# emission.net
KiCad netlist of a schematic drawn in EAGLE
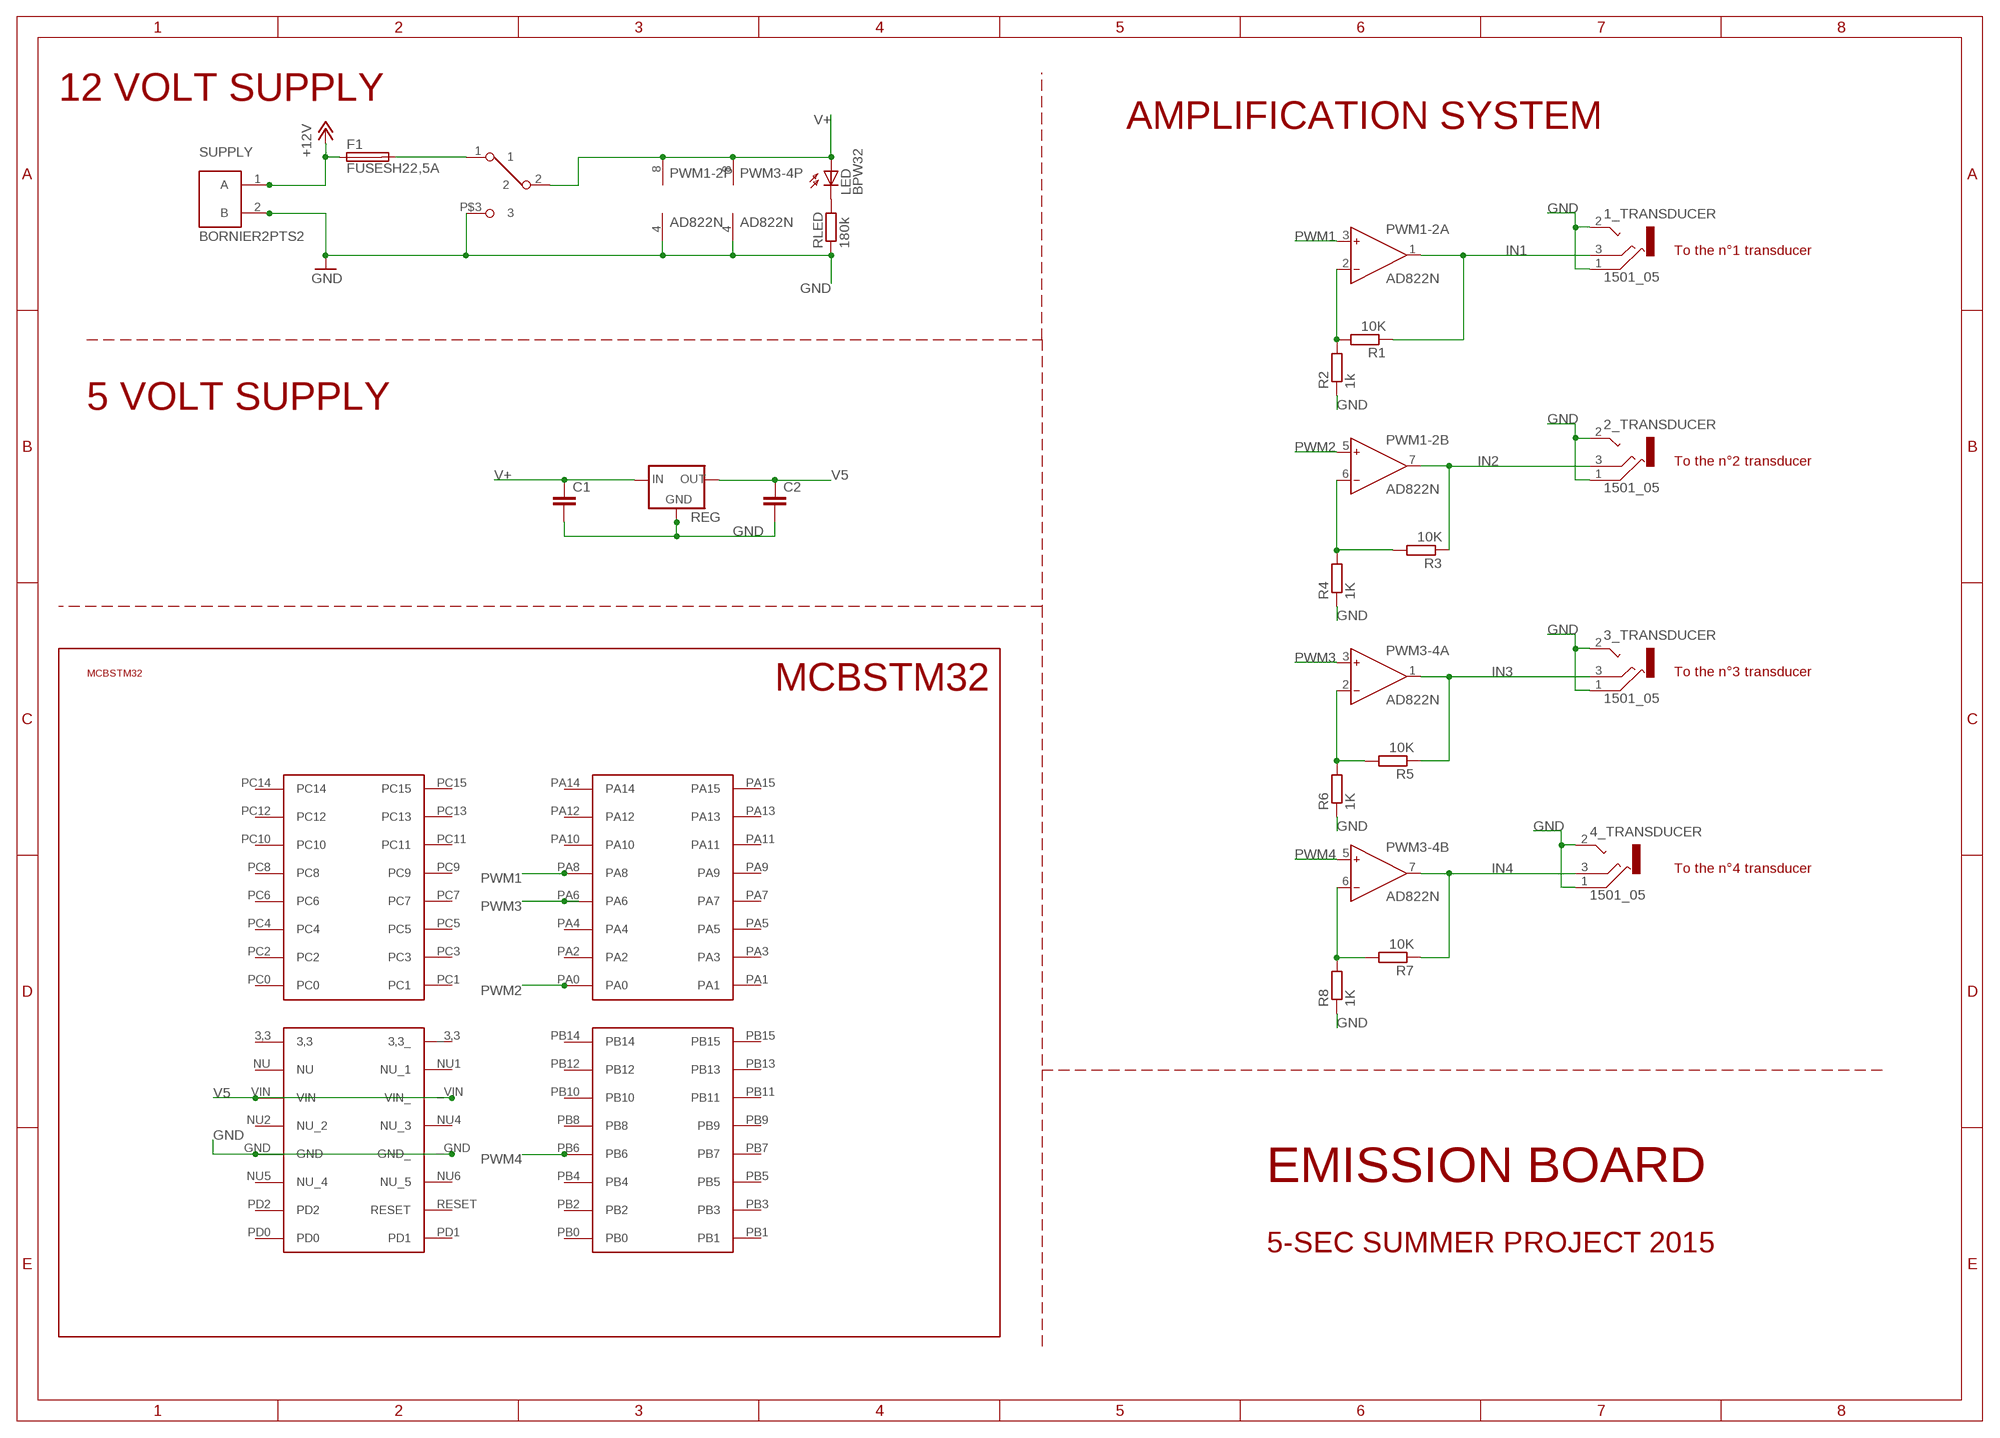
[diagram p0: schematic, sheet 1]

(export (version "E")
  (design (tool "Eeschema 10.0.6"))
  (components
    (comp (ref "1_TRANSDUCER")
      (value "1501_05")
      (footprint "eagle-import:1501_05")
      (libsource (lib "eagle-import") (part "1501_05"))
    )
    (comp (ref "2_TRANSDUCER")
      (value "1501_05")
      (footprint "eagle-import:1501_05")
      (libsource (lib "eagle-import") (part "1501_05"))
    )
    (comp (ref "3_TRANSDUCER")
      (value "1501_05")
      (footprint "eagle-import:1501_05")
      (libsource (lib "eagle-import") (part "1501_05"))
    )
    (comp (ref "4_TRANSDUCER")
      (value "1501_05")
      (footprint "eagle-import:1501_05")
      (libsource (lib "eagle-import") (part "1501_05"))
    )
    (comp (ref "C1")
      (value "C-EU050-030X075")
      (footprint "eagle-import:C050-030X075")
      (libsource (lib "eagle-import") (part "C-EU050-030X075"))
    )
    (comp (ref "C2")
      (value "C-EU050-030X075")
      (footprint "eagle-import:C050-030X075")
      (libsource (lib "eagle-import") (part "C-EU050-030X075"))
    )
    (comp (ref "F1")
      (value "FUSESH22,5A")
      (footprint "eagle-import:SH22,5A")
      (libsource (lib "eagle-import") (part "FUSESH22,5A"))
    )
    (comp (ref "LED")
      (value "BPW32")
      (footprint "eagle-import:BPW32")
      (libsource (lib "eagle-import") (part "BPW32"))
    )
    (comp (ref "MCBSTM1")
      (value "CONNECTOR_MCBSTM32")
      (footprint "eagle-import:CONNECTORSTM")
      (libsource (lib "eagle-import") (part "CONNECTOR_MCBSTM32"))
    )
    (comp (ref "PWM1-2")
      (value "AD822N")
      (footprint "eagle-import:DIL08")
      (libsource (lib "eagle-import") (part "AD822N"))
    )
    (comp (ref "PWM3-4")
      (value "AD822N")
      (footprint "eagle-import:DIL08")
      (libsource (lib "eagle-import") (part "AD822N"))
    )
    (comp (ref "R1")
      (value "10K")
      (footprint "eagle-import:P0613_15")
      (libsource (lib "eagle-import") (part "R-EU_0613/15"))
    )
    (comp (ref "R2")
      (value "1k")
      (footprint "eagle-import:P0613_15")
      (libsource (lib "eagle-import") (part "R-EU_0613/15"))
    )
    (comp (ref "R3")
      (value "10K")
      (footprint "eagle-import:P0613_15")
      (libsource (lib "eagle-import") (part "R-EU_0613/15"))
    )
    (comp (ref "R4")
      (value "1K")
      (footprint "eagle-import:P0613_15")
      (libsource (lib "eagle-import") (part "R-EU_0613/15"))
    )
    (comp (ref "R5")
      (value "10K")
      (footprint "eagle-import:P0613_15")
      (libsource (lib "eagle-import") (part "R-EU_0613/15"))
    )
    (comp (ref "R6")
      (value "1K")
      (footprint "eagle-import:P0613_15")
      (libsource (lib "eagle-import") (part "R-EU_0613/15"))
    )
    (comp (ref "R7")
      (value "10K")
      (footprint "eagle-import:P0613_15")
      (libsource (lib "eagle-import") (part "R-EU_0613/15"))
    )
    (comp (ref "R8")
      (value "1K")
      (footprint "eagle-import:P0613_15")
      (libsource (lib "eagle-import") (part "R-EU_0613/15"))
    )
    (comp (ref "REG")
      (value "78XXS")
      (footprint "eagle-import:78XXS")
      (libsource (lib "eagle-import") (part "78XXS"))
    )
    (comp (ref "RLED")
      (value "180k")
      (footprint "eagle-import:P0613_15")
      (libsource (lib "eagle-import") (part "resistor_R-EU_0613/15"))
    )
    (comp (ref "SUPPLY")
      (value "BORNIER2PTS2")
      (footprint "eagle-import:BORN2X5.08")
      (libsource (lib "eagle-import") (part "BORNIER2PTS2"))
    )
    (comp (ref "U$2")
      (value "SWITCH_CKCOMPONENT")
      (footprint "eagle-import:SWITCH_CKCOMPONENT")
      (libsource (lib "eagle-import") (part "SWITCH_CKCOMPONENT"))
    )
  )
  (nets
    (net (code "1") (name "+12V") (class "Default")
      (node (ref "F1") (pin "1") (pinfunction "1_1") (pintype "passive"))
      (node (ref "SUPPLY") (pin "1") (pinfunction "A_1") (pintype "bidirectional"))
    )
    (net (code "2") (name "/IN1") (class "Default")
      (node (ref "1_TRANSDUCER") (pin "3") (pinfunction "3_3") (pintype "passive"))
      (node (ref "PWM1-2") (pin "1") (pinfunction "OUT_1") (pintype "output"))
      (node (ref "R1") (pin "1") (pinfunction "1_1") (pintype "passive"))
    )
    (net (code "3") (name "/IN2") (class "Default")
      (node (ref "2_TRANSDUCER") (pin "3") (pinfunction "3_3") (pintype "passive"))
      (node (ref "PWM1-2") (pin "7") (pinfunction "OUT_7") (pintype "output"))
      (node (ref "R3") (pin "1") (pinfunction "1_1") (pintype "passive"))
    )
    (net (code "4") (name "/IN3") (class "Default")
      (node (ref "3_TRANSDUCER") (pin "3") (pinfunction "3_3") (pintype "passive"))
      (node (ref "PWM3-4") (pin "1") (pinfunction "OUT_1") (pintype "output"))
      (node (ref "R5") (pin "1") (pinfunction "1_1") (pintype "passive"))
    )
    (net (code "5") (name "/IN4") (class "Default")
      (node (ref "4_TRANSDUCER") (pin "3") (pinfunction "3_3") (pintype "passive"))
      (node (ref "PWM3-4") (pin "7") (pinfunction "OUT_7") (pintype "output"))
      (node (ref "R7") (pin "1") (pinfunction "1_1") (pintype "passive"))
    )
    (net (code "6") (name "/PWM1") (class "Default")
      (node (ref "MCBSTM1") (pin "PA8") (pinfunction "PA8_PA8") (pintype "bidirectional"))
      (node (ref "PWM1-2") (pin "3") (pinfunction "IN+_3") (pintype "input"))
    )
    (net (code "7") (name "/PWM2") (class "Default")
      (node (ref "MCBSTM1") (pin "PA0") (pinfunction "PA0_PA0") (pintype "bidirectional"))
      (node (ref "PWM1-2") (pin "5") (pinfunction "IN+_5") (pintype "input"))
    )
    (net (code "8") (name "/PWM3") (class "Default")
      (node (ref "MCBSTM1") (pin "PA6") (pinfunction "PA6_PA6") (pintype "bidirectional"))
      (node (ref "PWM3-4") (pin "3") (pinfunction "IN+_3") (pintype "input"))
    )
    (net (code "9") (name "/PWM4") (class "Default")
      (node (ref "MCBSTM1") (pin "PB6") (pinfunction "PB6_PB6") (pintype "bidirectional"))
      (node (ref "PWM3-4") (pin "5") (pinfunction "IN+_5") (pintype "input"))
    )
    (net (code "10") (name "/V+") (class "Default")
      (node (ref "C1") (pin "1") (pinfunction "1_1") (pintype "passive"))
      (node (ref "LED") (pin "A") (pinfunction "A_A") (pintype "passive"))
      (node (ref "PWM1-2") (pin "8") (pinfunction "V+_8") (pintype "power_in"))
      (node (ref "PWM3-4") (pin "8") (pinfunction "V+_8") (pintype "power_in"))
      (node (ref "REG") (pin "IN") (pinfunction "IN_IN") (pintype "input"))
      (node (ref "U$2") (pin "2") (pinfunction "2_2") (pintype "bidirectional"))
    )
    (net (code "11") (name "/V5") (class "Default")
      (node (ref "C2") (pin "1") (pinfunction "1_1") (pintype "passive"))
      (node (ref "MCBSTM1") (pin "VIN") (pinfunction "VIN_VIN") (pintype "bidirectional"))
      (node (ref "MCBSTM1") (pin "_VIN") (pinfunction "VIN___VIN") (pintype "bidirectional"))
      (node (ref "REG") (pin "OUT") (pinfunction "OUT_OUT") (pintype "passive"))
    )
    (net (code "12") (name "GND") (class "Default")
      (node (ref "1_TRANSDUCER") (pin "1") (pinfunction "1_1") (pintype "passive"))
      (node (ref "1_TRANSDUCER") (pin "2") (pinfunction "2_2") (pintype "passive"))
      (node (ref "2_TRANSDUCER") (pin "1") (pinfunction "1_1") (pintype "passive"))
      (node (ref "2_TRANSDUCER") (pin "2") (pinfunction "2_2") (pintype "passive"))
      (node (ref "3_TRANSDUCER") (pin "1") (pinfunction "1_1") (pintype "passive"))
      (node (ref "3_TRANSDUCER") (pin "2") (pinfunction "2_2") (pintype "passive"))
      (node (ref "4_TRANSDUCER") (pin "1") (pinfunction "1_1") (pintype "passive"))
      (node (ref "4_TRANSDUCER") (pin "2") (pinfunction "2_2") (pintype "passive"))
      (node (ref "C1") (pin "2") (pinfunction "2_2") (pintype "passive"))
      (node (ref "C2") (pin "2") (pinfunction "2_2") (pintype "passive"))
      (node (ref "MCBSTM1") (pin "GND") (pinfunction "GND_GND") (pintype "bidirectional"))
      (node (ref "MCBSTM1") (pin "_GND") (pinfunction "GND___GND") (pintype "bidirectional"))
      (node (ref "PWM1-2") (pin "4") (pinfunction "V-_4") (pintype "power_in"))
      (node (ref "PWM3-4") (pin "4") (pinfunction "V-_4") (pintype "power_in"))
      (node (ref "R2") (pin "1") (pinfunction "1_1") (pintype "passive"))
      (node (ref "R4") (pin "1") (pinfunction "1_1") (pintype "passive"))
      (node (ref "R6") (pin "1") (pinfunction "1_1") (pintype "passive"))
      (node (ref "R8") (pin "1") (pinfunction "1_1") (pintype "passive"))
      (node (ref "REG") (pin "GND") (pinfunction "GND_GND") (pintype "input"))
      (node (ref "RLED") (pin "1") (pinfunction "1_1") (pintype "passive"))
      (node (ref "SUPPLY") (pin "2") (pinfunction "B_2") (pintype "bidirectional"))
      (node (ref "U$2") (pin "P$3") (pinfunction "3_P$3") (pintype "bidirectional"))
    )
    (net (code "13") (name "Net-(F1-Pad2)") (class "Default")
      (node (ref "F1") (pin "2") (pinfunction "2_2") (pintype "passive"))
      (node (ref "U$2") (pin "1") (pinfunction "1_1") (pintype "bidirectional"))
    )
    (net (code "14") (name "Net-(LED-C)") (class "Default")
      (node (ref "LED") (pin "K") (pinfunction "C_K") (pintype "passive"))
      (node (ref "RLED") (pin "2") (pinfunction "2_2") (pintype "passive"))
    )
    (net (code "15") (name "Net-(PWM1-2A-IN-)") (class "Default")
      (node (ref "PWM1-2") (pin "2") (pinfunction "IN-_2") (pintype "input"))
      (node (ref "R1") (pin "2") (pinfunction "2_2") (pintype "passive"))
      (node (ref "R2") (pin "2") (pinfunction "2_2") (pintype "passive"))
    )
    (net (code "16") (name "Net-(PWM1-2B-IN-)") (class "Default")
      (node (ref "PWM1-2") (pin "6") (pinfunction "IN-_6") (pintype "input"))
      (node (ref "R3") (pin "2") (pinfunction "2_2") (pintype "passive"))
      (node (ref "R4") (pin "2") (pinfunction "2_2") (pintype "passive"))
    )
    (net (code "17") (name "Net-(PWM3-4A-IN-)") (class "Default")
      (node (ref "PWM3-4") (pin "2") (pinfunction "IN-_2") (pintype "input"))
      (node (ref "R5") (pin "2") (pinfunction "2_2") (pintype "passive"))
      (node (ref "R6") (pin "2") (pinfunction "2_2") (pintype "passive"))
    )
    (net (code "18") (name "Net-(PWM3-4B-IN-)") (class "Default")
      (node (ref "PWM3-4") (pin "6") (pinfunction "IN-_6") (pintype "input"))
      (node (ref "R7") (pin "2") (pinfunction "2_2") (pintype "passive"))
      (node (ref "R8") (pin "2") (pinfunction "2_2") (pintype "passive"))
    )
    (net (code "19") (name "unconnected-(MCBSTM1-3,3_-Pad_3,3)") (class "Default")
      (node (ref "MCBSTM1") (pin "_3,3") (pinfunction "3,3___3,3") (pintype "bidirectional"))
    )
    (net (code "20") (name "unconnected-(MCBSTM1-NU_1-PadNU1)") (class "Default")
      (node (ref "MCBSTM1") (pin "NU1") (pinfunction "NU_1_NU1") (pintype "bidirectional"))
    )
    (net (code "21") (name "unconnected-(MCBSTM1-NU_2-PadNU2)") (class "Default")
      (node (ref "MCBSTM1") (pin "NU2") (pinfunction "NU_2_NU2") (pintype "bidirectional"))
    )
    (net (code "22") (name "unconnected-(MCBSTM1-NU_3-PadNU4)") (class "Default")
      (node (ref "MCBSTM1") (pin "NU4") (pinfunction "NU_3_NU4") (pintype "bidirectional"))
    )
    (net (code "23") (name "unconnected-(MCBSTM1-NU_4-PadNU5)") (class "Default")
      (node (ref "MCBSTM1") (pin "NU5") (pinfunction "NU_4_NU5") (pintype "bidirectional"))
    )
    (net (code "24") (name "unconnected-(MCBSTM1-NU_5-PadNU6)") (class "Default")
      (node (ref "MCBSTM1") (pin "NU6") (pinfunction "NU_5_NU6") (pintype "bidirectional"))
    )
    (net (code "25") (name "unconnected-(MCBSTM1-Pad3,3)") (class "Default")
      (node (ref "MCBSTM1") (pin "3,3") (pinfunction "3,3_3,3") (pintype "bidirectional"))
    )
    (net (code "26") (name "unconnected-(MCBSTM1-PadNU)") (class "Default")
      (node (ref "MCBSTM1") (pin "NU") (pinfunction "NU_NU") (pintype "bidirectional"))
    )
    (net (code "27") (name "unconnected-(MCBSTM1-PadPA1)") (class "Default")
      (node (ref "MCBSTM1") (pin "PA1") (pinfunction "PA1_PA1") (pintype "bidirectional"))
    )
    (net (code "28") (name "unconnected-(MCBSTM1-PadPA2)") (class "Default")
      (node (ref "MCBSTM1") (pin "PA2") (pinfunction "PA2_PA2") (pintype "bidirectional"))
    )
    (net (code "29") (name "unconnected-(MCBSTM1-PadPA3)") (class "Default")
      (node (ref "MCBSTM1") (pin "PA3") (pinfunction "PA3_PA3") (pintype "bidirectional"))
    )
    (net (code "30") (name "unconnected-(MCBSTM1-PadPA4)") (class "Default")
      (node (ref "MCBSTM1") (pin "PA4") (pinfunction "PA4_PA4") (pintype "bidirectional"))
    )
    (net (code "31") (name "unconnected-(MCBSTM1-PadPA5)") (class "Default")
      (node (ref "MCBSTM1") (pin "PA5") (pinfunction "PA5_PA5") (pintype "bidirectional"))
    )
    (net (code "32") (name "unconnected-(MCBSTM1-PadPA7)") (class "Default")
      (node (ref "MCBSTM1") (pin "PA7") (pinfunction "PA7_PA7") (pintype "bidirectional"))
    )
    (net (code "33") (name "unconnected-(MCBSTM1-PadPA9)") (class "Default")
      (node (ref "MCBSTM1") (pin "PA9") (pinfunction "PA9_PA9") (pintype "bidirectional"))
    )
    (net (code "34") (name "unconnected-(MCBSTM1-PadPA10)") (class "Default")
      (node (ref "MCBSTM1") (pin "PA10") (pinfunction "PA10_PA10") (pintype "bidirectional"))
    )
    (net (code "35") (name "unconnected-(MCBSTM1-PadPA11)") (class "Default")
      (node (ref "MCBSTM1") (pin "PA11") (pinfunction "PA11_PA11") (pintype "bidirectional"))
    )
    (net (code "36") (name "unconnected-(MCBSTM1-PadPA12)") (class "Default")
      (node (ref "MCBSTM1") (pin "PA12") (pinfunction "PA12_PA12") (pintype "bidirectional"))
    )
    (net (code "37") (name "unconnected-(MCBSTM1-PadPA13)") (class "Default")
      (node (ref "MCBSTM1") (pin "PA13") (pinfunction "PA13_PA13") (pintype "bidirectional"))
    )
    (net (code "38") (name "unconnected-(MCBSTM1-PadPA14)") (class "Default")
      (node (ref "MCBSTM1") (pin "PA14") (pinfunction "PA14_PA14") (pintype "bidirectional"))
    )
    (net (code "39") (name "unconnected-(MCBSTM1-PadPA15)") (class "Default")
      (node (ref "MCBSTM1") (pin "PA15") (pinfunction "PA15_PA15") (pintype "bidirectional"))
    )
    (net (code "40") (name "unconnected-(MCBSTM1-PadPB0)") (class "Default")
      (node (ref "MCBSTM1") (pin "PB0") (pinfunction "PB0_PB0") (pintype "bidirectional"))
    )
    (net (code "41") (name "unconnected-(MCBSTM1-PadPB1)") (class "Default")
      (node (ref "MCBSTM1") (pin "PB1") (pinfunction "PB1_PB1") (pintype "bidirectional"))
    )
    (net (code "42") (name "unconnected-(MCBSTM1-PadPB2)") (class "Default")
      (node (ref "MCBSTM1") (pin "PB2") (pinfunction "PB2_PB2") (pintype "bidirectional"))
    )
    (net (code "43") (name "unconnected-(MCBSTM1-PadPB3)") (class "Default")
      (node (ref "MCBSTM1") (pin "PB3") (pinfunction "PB3_PB3") (pintype "bidirectional"))
    )
    (net (code "44") (name "unconnected-(MCBSTM1-PadPB4)") (class "Default")
      (node (ref "MCBSTM1") (pin "PB4") (pinfunction "PB4_PB4") (pintype "bidirectional"))
    )
    (net (code "45") (name "unconnected-(MCBSTM1-PadPB5)") (class "Default")
      (node (ref "MCBSTM1") (pin "PB5") (pinfunction "PB5_PB5") (pintype "bidirectional"))
    )
    (net (code "46") (name "unconnected-(MCBSTM1-PadPB7)") (class "Default")
      (node (ref "MCBSTM1") (pin "PB7") (pinfunction "PB7_PB7") (pintype "bidirectional"))
    )
    (net (code "47") (name "unconnected-(MCBSTM1-PadPB8)") (class "Default")
      (node (ref "MCBSTM1") (pin "PB8") (pinfunction "PB8_PB8") (pintype "bidirectional"))
    )
    (net (code "48") (name "unconnected-(MCBSTM1-PadPB9)") (class "Default")
      (node (ref "MCBSTM1") (pin "PB9") (pinfunction "PB9_PB9") (pintype "bidirectional"))
    )
    (net (code "49") (name "unconnected-(MCBSTM1-PadPB10)") (class "Default")
      (node (ref "MCBSTM1") (pin "PB10") (pinfunction "PB10_PB10") (pintype "bidirectional"))
    )
    (net (code "50") (name "unconnected-(MCBSTM1-PadPB11)") (class "Default")
      (node (ref "MCBSTM1") (pin "PB11") (pinfunction "PB11_PB11") (pintype "bidirectional"))
    )
    (net (code "51") (name "unconnected-(MCBSTM1-PadPB12)") (class "Default")
      (node (ref "MCBSTM1") (pin "PB12") (pinfunction "PB12_PB12") (pintype "bidirectional"))
    )
    (net (code "52") (name "unconnected-(MCBSTM1-PadPB13)") (class "Default")
      (node (ref "MCBSTM1") (pin "PB13") (pinfunction "PB13_PB13") (pintype "bidirectional"))
    )
    (net (code "53") (name "unconnected-(MCBSTM1-PadPB14)") (class "Default")
      (node (ref "MCBSTM1") (pin "PB14") (pinfunction "PB14_PB14") (pintype "bidirectional"))
    )
    (net (code "54") (name "unconnected-(MCBSTM1-PadPB15)") (class "Default")
      (node (ref "MCBSTM1") (pin "PB15") (pinfunction "PB15_PB15") (pintype "bidirectional"))
    )
    (net (code "55") (name "unconnected-(MCBSTM1-PadPC0)") (class "Default")
      (node (ref "MCBSTM1") (pin "PC0") (pinfunction "PC0_PC0") (pintype "bidirectional"))
    )
    (net (code "56") (name "unconnected-(MCBSTM1-PadPC1)") (class "Default")
      (node (ref "MCBSTM1") (pin "PC1") (pinfunction "PC1_PC1") (pintype "bidirectional"))
    )
    (net (code "57") (name "unconnected-(MCBSTM1-PadPC2)") (class "Default")
      (node (ref "MCBSTM1") (pin "PC2") (pinfunction "PC2_PC2") (pintype "bidirectional"))
    )
    (net (code "58") (name "unconnected-(MCBSTM1-PadPC3)") (class "Default")
      (node (ref "MCBSTM1") (pin "PC3") (pinfunction "PC3_PC3") (pintype "bidirectional"))
    )
    (net (code "59") (name "unconnected-(MCBSTM1-PadPC4)") (class "Default")
      (node (ref "MCBSTM1") (pin "PC4") (pinfunction "PC4_PC4") (pintype "bidirectional"))
    )
    (net (code "60") (name "unconnected-(MCBSTM1-PadPC5)") (class "Default")
      (node (ref "MCBSTM1") (pin "PC5") (pinfunction "PC5_PC5") (pintype "bidirectional"))
    )
    (net (code "61") (name "unconnected-(MCBSTM1-PadPC6)") (class "Default")
      (node (ref "MCBSTM1") (pin "PC6") (pinfunction "PC6_PC6") (pintype "bidirectional"))
    )
    (net (code "62") (name "unconnected-(MCBSTM1-PadPC7)") (class "Default")
      (node (ref "MCBSTM1") (pin "PC7") (pinfunction "PC7_PC7") (pintype "bidirectional"))
    )
    (net (code "63") (name "unconnected-(MCBSTM1-PadPC8)") (class "Default")
      (node (ref "MCBSTM1") (pin "PC8") (pinfunction "PC8_PC8") (pintype "bidirectional"))
    )
    (net (code "64") (name "unconnected-(MCBSTM1-PadPC9)") (class "Default")
      (node (ref "MCBSTM1") (pin "PC9") (pinfunction "PC9_PC9") (pintype "bidirectional"))
    )
    (net (code "65") (name "unconnected-(MCBSTM1-PadPC10)") (class "Default")
      (node (ref "MCBSTM1") (pin "PC10") (pinfunction "PC10_PC10") (pintype "bidirectional"))
    )
    (net (code "66") (name "unconnected-(MCBSTM1-PadPC11)") (class "Default")
      (node (ref "MCBSTM1") (pin "PC11") (pinfunction "PC11_PC11") (pintype "bidirectional"))
    )
    (net (code "67") (name "unconnected-(MCBSTM1-PadPC12)") (class "Default")
      (node (ref "MCBSTM1") (pin "PC12") (pinfunction "PC12_PC12") (pintype "bidirectional"))
    )
    (net (code "68") (name "unconnected-(MCBSTM1-PadPC13)") (class "Default")
      (node (ref "MCBSTM1") (pin "PC13") (pinfunction "PC13_PC13") (pintype "bidirectional"))
    )
    (net (code "69") (name "unconnected-(MCBSTM1-PadPC14)") (class "Default")
      (node (ref "MCBSTM1") (pin "PC14") (pinfunction "PC14_PC14") (pintype "bidirectional"))
    )
    (net (code "70") (name "unconnected-(MCBSTM1-PadPC15)") (class "Default")
      (node (ref "MCBSTM1") (pin "PC15") (pinfunction "PC15_PC15") (pintype "bidirectional"))
    )
    (net (code "71") (name "unconnected-(MCBSTM1-PadPD0)") (class "Default")
      (node (ref "MCBSTM1") (pin "PD0") (pinfunction "PD0_PD0") (pintype "bidirectional"))
    )
    (net (code "72") (name "unconnected-(MCBSTM1-PadPD1)") (class "Default")
      (node (ref "MCBSTM1") (pin "PD1") (pinfunction "PD1_PD1") (pintype "bidirectional"))
    )
    (net (code "73") (name "unconnected-(MCBSTM1-PadPD2)") (class "Default")
      (node (ref "MCBSTM1") (pin "PD2") (pinfunction "PD2_PD2") (pintype "bidirectional"))
    )
    (net (code "74") (name "unconnected-(MCBSTM1-PadRESET)") (class "Default")
      (node (ref "MCBSTM1") (pin "RESET") (pinfunction "RESET_RESET") (pintype "bidirectional"))
    )
  )
)
